# TFT.net
KiCad netlist of a schematic drawn in EAGLE
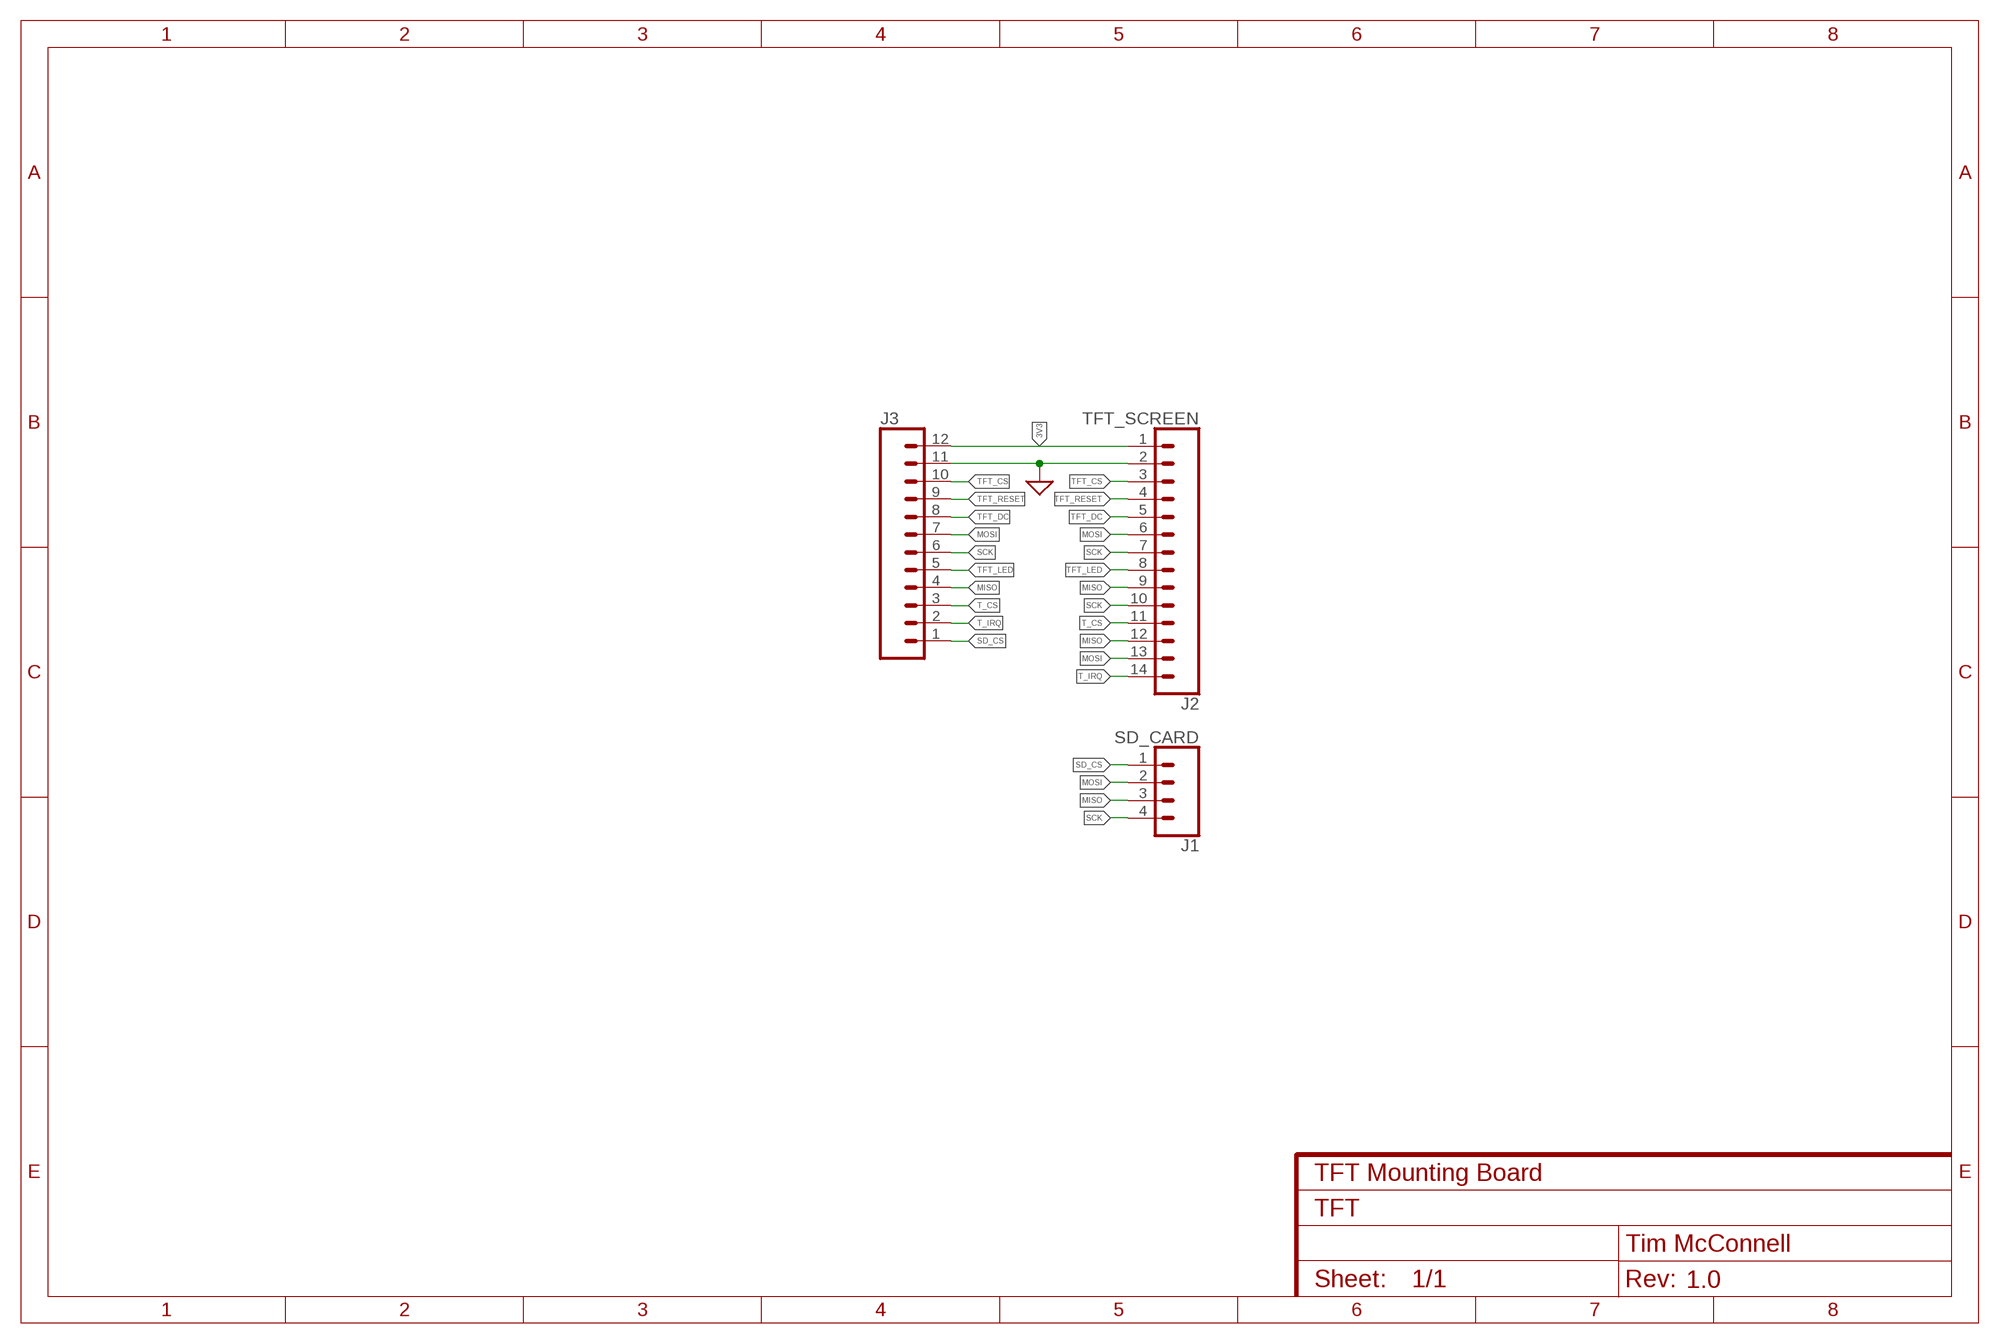
[diagram p0: schematic, sheet 1]

(export (version "E")
  (design (tool "Eeschema 10.0.6"))
  (components
    (comp (ref "J1")
      (value "SD_CARD")
      (footprint "eagle-import:1X04")
      (libsource (lib "eagle-import") (part "CONN_04"))
    )
    (comp (ref "J2")
      (value "TFT_SCREEN")
      (footprint "eagle-import:1X14")
      (libsource (lib "eagle-import") (part "CONN_14"))
    )
    (comp (ref "J3")
      (value "CONN_12")
      (footprint "eagle-import:1X12")
      (libsource (lib "eagle-import") (part "CONN_12"))
    )
  )
  (nets
    (net (code "1") (name "3V3") (class "Default")
      (node (ref "J2") (pin "1") (pinfunction "1_1") (pintype "passive"))
      (node (ref "J3") (pin "12") (pinfunction "12_12") (pintype "passive"))
    )
    (net (code "2") (name "MISO") (class "Default")
      (node (ref "J1") (pin "3") (pinfunction "3_3") (pintype "passive"))
      (node (ref "J2") (pin "12") (pinfunction "12_12") (pintype "passive"))
      (node (ref "J2") (pin "9") (pinfunction "9_9") (pintype "passive"))
      (node (ref "J3") (pin "4") (pinfunction "4_4") (pintype "passive"))
    )
    (net (code "3") (name "MOSI") (class "Default")
      (node (ref "J1") (pin "2") (pinfunction "2_2") (pintype "passive"))
      (node (ref "J2") (pin "13") (pinfunction "13_13") (pintype "passive"))
      (node (ref "J2") (pin "6") (pinfunction "6_6") (pintype "passive"))
      (node (ref "J3") (pin "7") (pinfunction "7_7") (pintype "passive"))
    )
    (net (code "4") (name "SCK") (class "Default")
      (node (ref "J1") (pin "4") (pinfunction "4_4") (pintype "passive"))
      (node (ref "J2") (pin "10") (pinfunction "10_10") (pintype "passive"))
      (node (ref "J2") (pin "7") (pinfunction "7_7") (pintype "passive"))
      (node (ref "J3") (pin "6") (pinfunction "6_6") (pintype "passive"))
    )
    (net (code "5") (name "SD_CS") (class "Default")
      (node (ref "J1") (pin "1") (pinfunction "1_1") (pintype "passive"))
      (node (ref "J3") (pin "1") (pinfunction "1_1") (pintype "passive"))
    )
    (net (code "6") (name "SUP") (class "Default")
      (node (ref "J2") (pin "2") (pinfunction "2_2") (pintype "passive"))
      (node (ref "J3") (pin "11") (pinfunction "11_11") (pintype "passive"))
    )
    (net (code "7") (name "TFT_CS") (class "Default")
      (node (ref "J2") (pin "3") (pinfunction "3_3") (pintype "passive"))
      (node (ref "J3") (pin "10") (pinfunction "10_10") (pintype "passive"))
    )
    (net (code "8") (name "TFT_DC") (class "Default")
      (node (ref "J2") (pin "5") (pinfunction "5_5") (pintype "passive"))
      (node (ref "J3") (pin "8") (pinfunction "8_8") (pintype "passive"))
    )
    (net (code "9") (name "TFT_LED") (class "Default")
      (node (ref "J2") (pin "8") (pinfunction "8_8") (pintype "passive"))
      (node (ref "J3") (pin "5") (pinfunction "5_5") (pintype "passive"))
    )
    (net (code "10") (name "TFT_RESET") (class "Default")
      (node (ref "J2") (pin "4") (pinfunction "4_4") (pintype "passive"))
      (node (ref "J3") (pin "9") (pinfunction "9_9") (pintype "passive"))
    )
    (net (code "11") (name "T_CS") (class "Default")
      (node (ref "J2") (pin "11") (pinfunction "11_11") (pintype "passive"))
      (node (ref "J3") (pin "3") (pinfunction "3_3") (pintype "passive"))
    )
    (net (code "12") (name "T_IRQ") (class "Default")
      (node (ref "J2") (pin "14") (pinfunction "14_14") (pintype "passive"))
      (node (ref "J3") (pin "2") (pinfunction "2_2") (pintype "passive"))
    )
  )
)
